# Main.net
KiCad netlist of a schematic drawn in Altium Designer
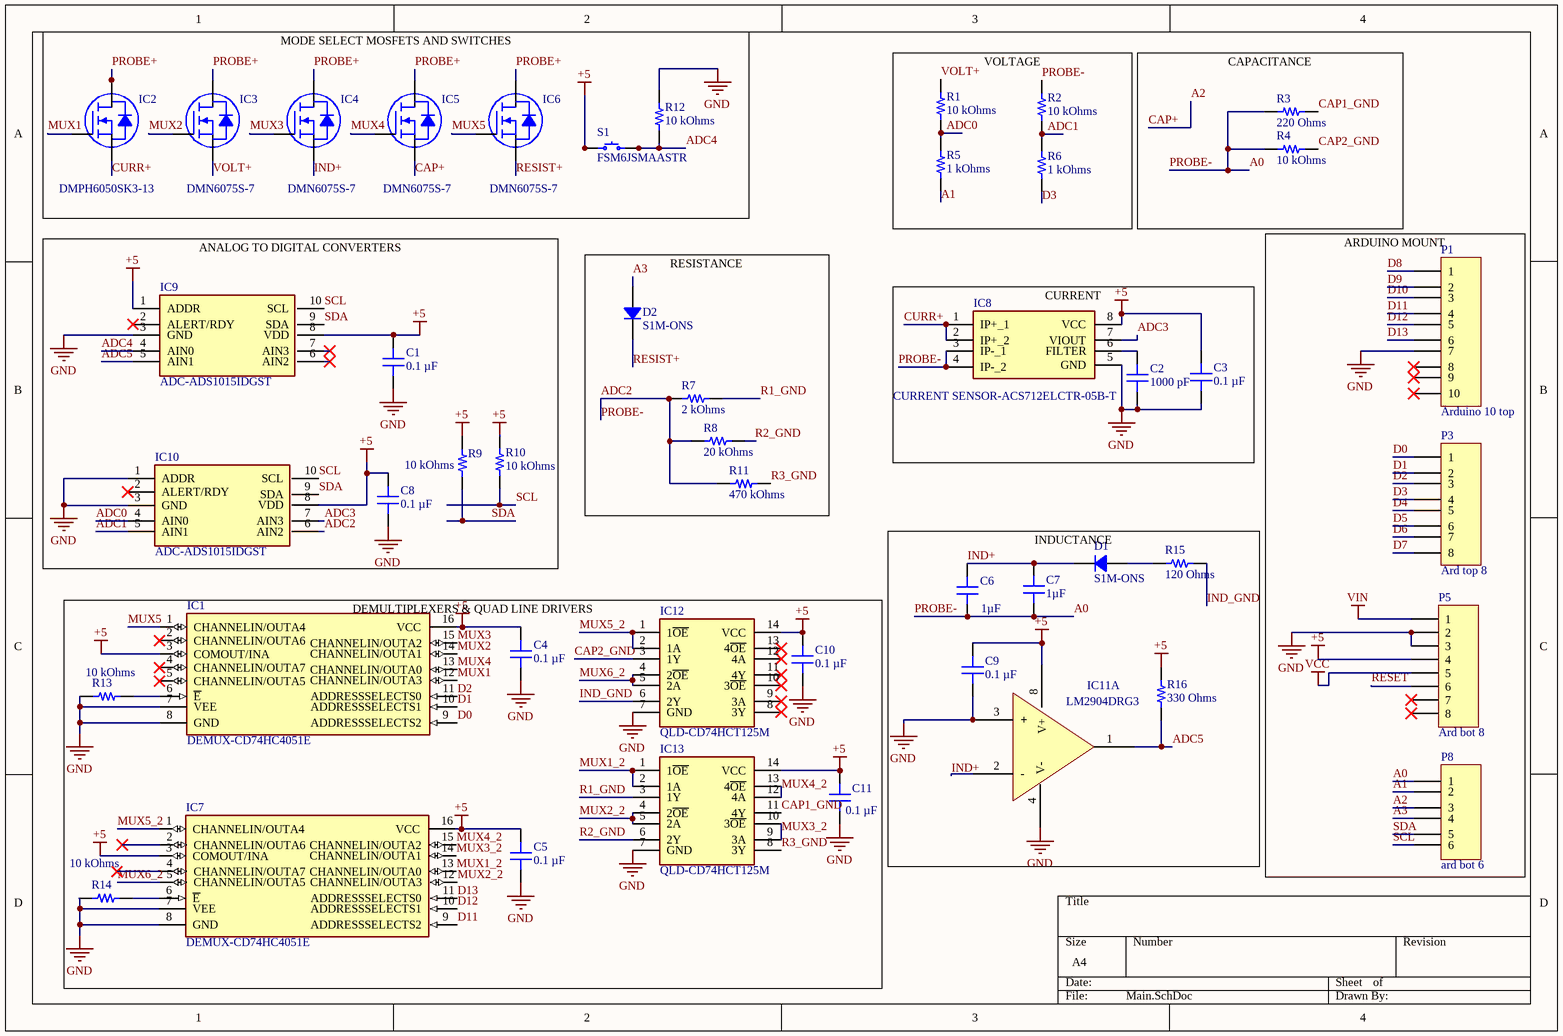
[diagram p0: Main.SchDoc]

(export (version "E")
  (design (tool "Eeschema 10.0.6"))
  (components
    (comp (ref "C1")
      (value "0.1 µF")
      (footprint "CAP 0805_2012")
      (description "CAP CER 0.1UF 50V X7R 0805")
      (fields
        (field (name "PART NUMBER") "CC0805MRX7R9BB104")
        (field (name "CAPACITANCE") "0.1 µF")
        (field (name "MANUFACTURER") "Yageo")
      )
      (libsource (lib "Celestial Altium Library - altium_library") (part "Capacitor"))
    )
    (comp (ref "C2")
      (value "1000 pF")
      (footprint "CAP 0805_2012")
      (description "CAP CER 1000PF 200V X7R 0805")
      (fields
        (field (name "PART NUMBER") "KGM21NR72D102KT")
        (field (name "CAPACITANCE") "1000 pF")
        (field (name "MANUFACTURER") "KYOCERA AVX")
      )
      (libsource (lib "Celestial Altium Library - altium_library") (part "Capacitor"))
    )
    (comp (ref "C3")
      (value "0.1 µF")
      (footprint "CAP 0805_2012")
      (description "CAP CER 0.1UF 50V X7R 0805")
      (fields
        (field (name "PART NUMBER") "CC0805MRX7R9BB104")
        (field (name "CAPACITANCE") "0.1 µF")
        (field (name "MANUFACTURER") "Yageo")
      )
      (libsource (lib "Celestial Altium Library - altium_library") (part "Capacitor"))
    )
    (comp (ref "C4")
      (value "0.1 µF")
      (footprint "CAP 0805_2012")
      (description "CAP CER 0.1UF 50V X7R 0805")
      (fields
        (field (name "PART NUMBER") "CC0805MRX7R9BB104")
        (field (name "CAPACITANCE") "0.1 µF")
        (field (name "MANUFACTURER") "Yageo")
      )
      (libsource (lib "Celestial Altium Library - altium_library") (part "Capacitor"))
    )
    (comp (ref "C5")
      (value "0.1 µF")
      (footprint "CAP 0805_2012")
      (description "CAP CER 0.1UF 50V X7R 0805")
      (fields
        (field (name "PART NUMBER") "CC0805MRX7R9BB104")
        (field (name "CAPACITANCE") "0.1 µF")
        (field (name "MANUFACTURER") "Yageo")
      )
      (libsource (lib "Celestial Altium Library - altium_library") (part "Capacitor"))
    )
    (comp (ref "C6")
      (value "1µF")
      (footprint "CAP 0805_2012")
      (description "CAP CER 1UF 10V X7R 0805")
      (fields
        (field (name "PART NUMBER") "MM05ZC105KCZ2A")
        (field (name "CAPACITANCE") "1µF")
        (field (name "MANUFACTURER") "AVX Corporation")
      )
      (libsource (lib "Celestial Altium Library - altium_library") (part "Capacitor"))
    )
    (comp (ref "C7")
      (value "1µF")
      (footprint "CAP 0805_2012")
      (description "CAP CER 1UF 10V X7R 0805")
      (fields
        (field (name "PART NUMBER") "MM05ZC105KCZ2A")
        (field (name "CAPACITANCE") "1µF")
        (field (name "MANUFACTURER") "AVX Corporation")
      )
      (libsource (lib "Celestial Altium Library - altium_library") (part "Capacitor"))
    )
    (comp (ref "C8")
      (value "0.1 µF")
      (footprint "CAP 0805_2012")
      (description "CAP CER 0.1UF 50V X7R 0805")
      (fields
        (field (name "PART NUMBER") "CC0805MRX7R9BB104")
        (field (name "CAPACITANCE") "0.1 µF")
        (field (name "MANUFACTURER") "Yageo")
      )
      (libsource (lib "Celestial Altium Library - altium_library") (part "Capacitor"))
    )
    (comp (ref "C9")
      (value "0.1 µF")
      (footprint "CAP 0805_2012")
      (description "CAP CER 0.1UF 50V X7R 0805")
      (fields
        (field (name "PART NUMBER") "CC0805MRX7R9BB104")
        (field (name "CAPACITANCE") "0.1 µF")
        (field (name "MANUFACTURER") "Yageo")
      )
      (libsource (lib "Celestial Altium Library - altium_library") (part "Capacitor"))
    )
    (comp (ref "C10")
      (value "0.1 µF")
      (footprint "CAP 0805_2012")
      (description "CAP CER 0.1UF 50V X7R 0805")
      (fields
        (field (name "PART NUMBER") "CC0805MRX7R9BB104")
        (field (name "CAPACITANCE") "0.1 µF")
        (field (name "MANUFACTURER") "Yageo")
      )
      (libsource (lib "Celestial Altium Library - altium_library") (part "Capacitor"))
    )
    (comp (ref "C11")
      (value "0.1 µF")
      (footprint "CAP 0805_2012")
      (description "CAP CER 0.1UF 50V X7R 0805")
      (fields
        (field (name "PART NUMBER") "CC0805MRX7R9BB104")
        (field (name "CAPACITANCE") "0.1 µF")
        (field (name "MANUFACTURER") "Yageo")
      )
      (libsource (lib "Celestial Altium Library - altium_library") (part "Capacitor"))
    )
    (comp (ref "D1")
      (value "S1M-ONS")
      (footprint "DO214AC SMA")
      (description "DIODE GEN PURP 50V 1A SMA")
      (fields (field (name "PART NUMBER") "RS1A") (field (name "MANUFACTURER") "ON Semiconductor"))
      (libsource (lib "Celestial Altium Library - altium_library") (part "Diode"))
    )
    (comp (ref "D2")
      (value "S1M-ONS")
      (footprint "DO214AC SMA")
      (description "DIODE GEN PURP 50V 1A SMA")
      (fields (field (name "PART NUMBER") "RS1A") (field (name "MANUFACTURER") "ON Semiconductor"))
      (libsource (lib "Celestial Altium Library - altium_library") (part "Diode"))
    )
    (comp (ref "IC1")
      (value "DEMUX-CD74HC4051E")
      (footprint "SamacSys:DIP794W53P254L1930H508Q16N")
      (description "Integrated Circuit")
      (fields
        (field (name "MANUFACTURER_PART_NUMBER") "CD74HC4051E")
        (field (name "MOUSER PART NUMBER") "595-CD74HC4051E")
      )
      (libsource (lib "*") (part "CD74HC4051E"))
    )
    (comp (ref "IC2")
      (value "DMPH6050SK3-13")
      (footprint "INFINEON PG-TO 252 GDS FET")
      (description "MOSFET N-CH 800V 1.9A TO252-3")
      (fields
        (field (name "PART NUMBER") "IPD80R2K8CEATMA1")
        (field (name "MANUFACTURER") "Infineon Technologies")
      )
      (libsource (lib "Celestial Altium Library - altium_library") (part "MOSFET SINGLE GDS"))
    )
    (comp (ref "IC3")
      (value "DMN6075S-7")
      (footprint "DIODES SOT-23-3")
      (description "MOSFET N-CH 60V 2A SOT23")
      (fields (field (name "MANUFACTURER") "Diodes Incorporated"))
      (libsource (lib "Celestial Altium Library - altium_library") (part "DIODES INC MOSFET N-CH SOT-23-3"))
    )
    (comp (ref "IC4")
      (value "DMN6075S-7")
      (footprint "DIODES SOT-23-3")
      (description "MOSFET N-CH 60V 2A SOT23")
      (fields (field (name "MANUFACTURER") "Diodes Incorporated"))
      (libsource (lib "Celestial Altium Library - altium_library") (part "DIODES INC MOSFET N-CH SOT-23-3"))
    )
    (comp (ref "IC5")
      (value "DMN6075S-7")
      (footprint "DIODES SOT-23-3")
      (description "MOSFET N-CH 60V 2A SOT23")
      (fields (field (name "MANUFACTURER") "Diodes Incorporated"))
      (libsource (lib "Celestial Altium Library - altium_library") (part "DIODES INC MOSFET N-CH SOT-23-3"))
    )
    (comp (ref "IC6")
      (value "DMN6075S-7")
      (footprint "DIODES SOT-23-3")
      (description "MOSFET N-CH 60V 2A SOT23")
      (fields (field (name "MANUFACTURER") "Diodes Incorporated"))
      (libsource (lib "Celestial Altium Library - altium_library") (part "DIODES INC MOSFET N-CH SOT-23-3"))
    )
    (comp (ref "IC7")
      (value "DEMUX-CD74HC4051E")
      (footprint "SamacSys:DIP794W53P254L1930H508Q16N")
      (description "Integrated Circuit")
      (fields
        (field (name "MANUFACTURER_PART_NUMBER") "CD74HC4051E")
        (field (name "MOUSER PART NUMBER") "595-CD74HC4051E")
      )
      (libsource (lib "") (part "CD74HC4051E_1"))
    )
    (comp (ref "IC8")
      (value "CURRENT SENSOR-ACS712ELCTR-05B-T")
      (footprint "SamacSys:SOIC127P600X175-8N")
      (description "Integrated Circuit")
      (fields
        (field (name "MANUFACTURER_PART_NUMBER") "ACS712ELCTR-05B-T")
        (field (name "MOUSER PART NUMBER") "250-712ELCTR05BT")
      )
      (libsource (lib "*") (part "ACS712ELCTR-05B-T"))
    )
    (comp (ref "IC9")
      (value "ADC-ADS1015IDGST")
      (footprint "SamacSys:SOP50P490X110-10N")
      (description "Integrated Circuit")
      (fields
        (field (name "MANUFACTURER_PART_NUMBER") "ADS1015IDGST")
        (field (name "MOUSER PART NUMBER") "595-ADS1015IDGST")
      )
      (libsource (lib "") (part "ADS1015IDGST_1"))
    )
    (comp (ref "IC10")
      (value "ADC-ADS1015IDGST")
      (footprint "SamacSys:SOP50P490X110-10N")
      (description "Integrated Circuit")
      (fields
        (field (name "MANUFACTURER_PART_NUMBER") "ADS1015IDGST")
        (field (name "MOUSER PART NUMBER") "595-ADS1015IDGST")
      )
      (libsource (lib "*") (part "ADS1015IDGST"))
    )
    (comp (ref "IC11")
      (value "LM2904DRG3")
      (footprint "TI SOIC-8 D")
      (description "IC OPAMP GP 2 CIRCUIT 8SOIC")
      (fields (field (name "MANUFACTURER") "Texas Instruments"))
      (libsource (lib "Celestial Altium Library - altium_library") (part "TI LM2904DR"))
    )
    (comp (ref "IC12")
      (value "QLD-CD74HCT125M")
      (footprint "SamacSys:SOIC127P600X175-14N")
      (description "Integrated Circuit")
      (fields
        (field (name "MANUFACTURER_PART_NUMBER") "CD74HCT125M")
        (field (name "MOUSER PART NUMBER") "595-CD74HCT125M")
      )
      (libsource (lib "*") (part "CD74HCT125M"))
    )
    (comp (ref "IC13")
      (value "QLD-CD74HCT125M")
      (footprint "SamacSys:SOIC127P600X175-14N")
      (description "Integrated Circuit")
      (fields
        (field (name "MANUFACTURER_PART_NUMBER") "CD74HCT125M")
        (field (name "MOUSER PART NUMBER") "595-CD74HCT125M")
      )
      (libsource (lib "") (part "CD74HCT125M_1"))
    )
    (comp (ref "P1")
      (value "Arduino 10 top")
      (footprint "HDR1X10")
      (description "Header, 10-Pin")
      (fields (field (name "PUBLISHER") "Altium Limited"))
      (libsource (lib "Miscellaneous Connectors") (part "Header 10"))
    )
    (comp (ref "P3")
      (value "Ard top 8")
      (footprint "HDR1X8")
      (description "Header, 8-Pin")
      (fields (field (name "PUBLISHER") "Altium Limited"))
      (libsource (lib "") (part "Header 8_1"))
    )
    (comp (ref "P5")
      (value "Ard bot 8")
      (footprint "HDR1X8")
      (description "Header, 8-Pin")
      (fields (field (name "PUBLISHER") "Altium Limited"))
      (libsource (lib "Miscellaneous Connectors") (part "Header 8"))
    )
    (comp (ref "P8")
      (value "ard bot 6")
      (footprint "HDR1X6")
      (description "Header, 6-Pin")
      (fields (field (name "PUBLISHER") "Altium Limited"))
      (libsource (lib "Miscellaneous Connectors") (part "Header 6"))
    )
    (comp (ref "R1")
      (value "10 kOhms")
      (footprint "RES 0805_2012")
      (description "RES 10K OHM 0.1% 1/10W 0805")
      (fields
        (field (name "PART NUMBER") "RNCS0805BKE10K0")
        (field (name "MANUFACTURER") "Stackpole Electronics Inc")
      )
      (libsource (lib "Celestial Altium Library - altium_library") (part "Resistor"))
    )
    (comp (ref "R2")
      (value "10 kOhms")
      (footprint "RES 0805_2012")
      (description "RES 10K OHM 0.1% 1/10W 0805")
      (fields
        (field (name "PART NUMBER") "RNCS0805BKE10K0")
        (field (name "MANUFACTURER") "Stackpole Electronics Inc")
      )
      (libsource (lib "Celestial Altium Library - altium_library") (part "Resistor"))
    )
    (comp (ref "R3")
      (value "220 Ohms")
      (footprint "RES 0805_2012")
      (description "RES SMD 220 OHM 1% 0.4W 0805")
      (fields (field (name "PART NUMBER") "ESR10EZPF2200") (field (name "MANUFACTURER") "Rohm Semiconductor"))
      (libsource (lib "Celestial Altium Library - altium_library") (part "Resistor"))
    )
    (comp (ref "R4")
      (value "10 kOhms")
      (footprint "RES 0805_2012")
      (description "RES 10K OHM 0.1% 1/10W 0805")
      (fields
        (field (name "PART NUMBER") "RNCS0805BKE10K0")
        (field (name "MANUFACTURER") "Stackpole Electronics Inc")
      )
      (libsource (lib "Celestial Altium Library - altium_library") (part "Resistor"))
    )
    (comp (ref "R5")
      (value "1 kOhms")
      (footprint "RES 0805_2012")
      (description "RES 10K OHM 0.1% 1/10W 0805")
      (fields
        (field (name "PART NUMBER") "RNCS0805BKE10K0")
        (field (name "MANUFACTURER") "Stackpole Electronics Inc")
      )
      (libsource (lib "Celestial Altium Library - altium_library") (part "Resistor"))
    )
    (comp (ref "R6")
      (value "1 kOhms")
      (footprint "RES 0805_2012")
      (description "RES 10K OHM 0.1% 1/10W 0805")
      (fields
        (field (name "PART NUMBER") "RNCS0805BKE10K0")
        (field (name "MANUFACTURER") "Stackpole Electronics Inc")
      )
      (libsource (lib "Celestial Altium Library - altium_library") (part "Resistor"))
    )
    (comp (ref "R7")
      (value "2 kOhms")
      (footprint "RES 0805_2012")
      (description "RES 10K OHM 0.1% 1/10W 0805")
      (fields
        (field (name "PART NUMBER") "RNCS0805BKE10K0")
        (field (name "MANUFACTURER") "Stackpole Electronics Inc")
      )
      (libsource (lib "Celestial Altium Library - altium_library") (part "Resistor"))
    )
    (comp (ref "R8")
      (value "20 kOhms")
      (footprint "RES 0805_2012")
      (description "RES 10K OHM 0.1% 1/10W 0805")
      (fields
        (field (name "PART NUMBER") "RNCS0805BKE10K0")
        (field (name "MANUFACTURER") "Stackpole Electronics Inc")
      )
      (libsource (lib "Celestial Altium Library - altium_library") (part "Resistor"))
    )
    (comp (ref "R9")
      (value "10 kOhms")
      (footprint "RES 0805_2012")
      (description "RES 10K OHM 0.1% 1/10W 0805")
      (fields
        (field (name "PART NUMBER") "RNCS0805BKE10K0")
        (field (name "MANUFACTURER") "Stackpole Electronics Inc")
      )
      (libsource (lib "Celestial Altium Library - altium_library") (part "Resistor"))
    )
    (comp (ref "R10")
      (value "10 kOhms")
      (footprint "RES 0805_2012")
      (description "RES 10K OHM 0.1% 1/10W 0805")
      (fields
        (field (name "PART NUMBER") "RNCS0805BKE10K0")
        (field (name "MANUFACTURER") "Stackpole Electronics Inc")
      )
      (libsource (lib "Celestial Altium Library - altium_library") (part "Resistor"))
    )
    (comp (ref "R11")
      (value "470 kOhms")
      (footprint "RES 0805_2012")
      (description "RES 10K OHM 0.1% 1/10W 0805")
      (fields
        (field (name "PART NUMBER") "RNCS0805BKE10K0")
        (field (name "MANUFACTURER") "Stackpole Electronics Inc")
      )
      (libsource (lib "Celestial Altium Library - altium_library") (part "Resistor"))
    )
    (comp (ref "R12")
      (value "10 kOhms")
      (footprint "RES 0805_2012")
      (description "RES 10K OHM 0.1% 1/10W 0805")
      (fields
        (field (name "PART NUMBER") "RNCS0805BKE10K0")
        (field (name "MANUFACTURER") "Stackpole Electronics Inc")
      )
      (libsource (lib "Celestial Altium Library - altium_library") (part "Resistor"))
    )
    (comp (ref "R13")
      (value "10 kOhms")
      (footprint "RES 0805_2012")
      (description "RES 10K OHM 0.1% 1/10W 0805")
      (fields
        (field (name "PART NUMBER") "RNCS0805BKE10K0")
        (field (name "MANUFACTURER") "Stackpole Electronics Inc")
      )
      (libsource (lib "Celestial Altium Library - altium_library") (part "Resistor"))
    )
    (comp (ref "R14")
      (value "10 kOhms")
      (footprint "RES 0805_2012")
      (description "RES 10K OHM 0.1% 1/10W 0805")
      (fields
        (field (name "PART NUMBER") "RNCS0805BKE10K0")
        (field (name "MANUFACTURER") "Stackpole Electronics Inc")
      )
      (libsource (lib "Celestial Altium Library - altium_library") (part "Resistor"))
    )
    (comp (ref "R15")
      (value "120 Ohms")
      (footprint "RES 0805_2012")
      (description "RES SMD 120 OHM 1% 1/8W 0805")
      (fields
        (field (name "PART NUMBER") "ERJ-6ENF1200V")
        (field (name "MANUFACTURER") "Panasonic Electronic Components")
      )
      (libsource (lib "Celestial Altium Library - altium_library") (part "Resistor"))
    )
    (comp (ref "R16")
      (value "330 Ohms")
      (footprint "RES 0805_2012")
      (description "RES SMD 330 OHM 1% 1/2W 0805")
      (fields (field (name "PART NUMBER") "CRCW0805330RFKEAHP") (field (name "MANUFACTURER") "Vishay Dale"))
      (libsource (lib "Celestial Altium Library - altium_library") (part "Resistor"))
    )
    (comp (ref "S1")
      (value "FSM6JSMAASTR")
      (footprint "TE FSM6JSMA")
      (description "SWITCH TACTILE SPST-NO 0.05A 24V")
      (fields (field (name "MANUFACTURER") "TE Connectivity ALCOSWITCH Switches"))
      (libsource (lib "Celestial Altium Library - altium_library") (part "SPST-NO 4 PIN"))
    )
  )
  (nets
    (net (code "1") (name "+5") (class "Default")
      (node (ref "C1") (pin "2") (pinfunction "2_2") (pintype "passive"))
      (node (ref "C10") (pin "2") (pinfunction "2_2") (pintype "passive"))
      (node (ref "C11") (pin "2") (pinfunction "2_2") (pintype "passive"))
      (node (ref "C3") (pin "2") (pinfunction "2_2") (pintype "passive"))
      (node (ref "C4") (pin "2") (pinfunction "2_2") (pintype "passive"))
      (node (ref "C5") (pin "2") (pinfunction "2_2") (pintype "passive"))
      (node (ref "C8") (pin "2") (pinfunction "2_2") (pintype "passive"))
      (node (ref "C9") (pin "2") (pinfunction "2_2") (pintype "passive"))
      (node (ref "IC1") (pin "16") (pinfunction "VCC_16") (pintype "power_in"))
      (node (ref "IC1") (pin "3") (pinfunction "COMOUT/INA_3") (pintype "bidirectional"))
      (node (ref "IC10") (pin "8") (pinfunction "VDD_8") (pintype "passive"))
      (node (ref "IC11") (pin "8") (pinfunction "V+_8") (pintype "passive"))
      (node (ref "IC12") (pin "14") (pinfunction "VCC_14") (pintype "passive"))
      (node (ref "IC13") (pin "14") (pinfunction "VCC_14") (pintype "passive"))
      (node (ref "IC7") (pin "16") (pinfunction "VCC_16") (pintype "power_in"))
      (node (ref "IC7") (pin "3") (pinfunction "COMOUT/INA_3") (pintype "bidirectional"))
      (node (ref "IC8") (pin "8") (pinfunction "VCC_8") (pintype "passive"))
      (node (ref "IC9") (pin "1") (pinfunction "ADDR_1") (pintype "passive"))
      (node (ref "IC9") (pin "8") (pinfunction "VDD_8") (pintype "passive"))
      (node (ref "P5") (pin "4") (pinfunction "4_4") (pintype "passive"))
      (node (ref "R10") (pin "2") (pinfunction "2_2") (pintype "passive"))
      (node (ref "R16") (pin "2") (pinfunction "2_2") (pintype "passive"))
      (node (ref "R9") (pin "2") (pinfunction "2_2") (pintype "passive"))
      (node (ref "S1") (pin "1") (pinfunction "1_1") (pintype "passive"))
      (node (ref "S1") (pin "2") (pinfunction "2_2") (pintype "passive"))
    )
    (net (code "2") (name "/A0") (class "Default")
      (node (ref "C6") (pin "1") (pinfunction "1_1") (pintype "passive"))
      (node (ref "C7") (pin "1") (pinfunction "1_1") (pintype "passive"))
      (node (ref "IC10") (pin "6") (pinfunction "AIN2_6") (pintype "passive"))
      (node (ref "IC8") (pin "3") (pinfunction "IP-_1_3") (pintype "passive"))
      (node (ref "IC8") (pin "4") (pinfunction "IP-_2_4") (pintype "passive"))
      (node (ref "P8") (pin "1") (pinfunction "1_1") (pintype "passive"))
      (node (ref "R11") (pin "2") (pinfunction "2_2") (pintype "passive"))
      (node (ref "R2") (pin "2") (pinfunction "2_2") (pintype "passive"))
      (node (ref "R3") (pin "1") (pinfunction "1_1") (pintype "passive"))
      (node (ref "R4") (pin "2") (pinfunction "2_2") (pintype "passive"))
      (node (ref "R7") (pin "2") (pinfunction "2_2") (pintype "passive"))
      (node (ref "R8") (pin "2") (pinfunction "2_2") (pintype "passive"))
    )
    (net (code "3") (name "/A1") (class "Default")
      (node (ref "P8") (pin "2") (pinfunction "2_2") (pintype "passive"))
      (node (ref "R5") (pin "1") (pinfunction "1_1") (pintype "passive"))
    )
    (net (code "4") (name "/A2") (class "Default")
      (node (ref "IC5") (pin "2") (pinfunction "S_2") (pintype "passive"))
      (node (ref "P8") (pin "3") (pinfunction "3_3") (pintype "passive"))
    )
    (net (code "5") (name "/A3") (class "Default")
      (node (ref "D2") (pin "1") (pinfunction "1_1") (pintype "passive"))
      (node (ref "P8") (pin "4") (pinfunction "4_4") (pintype "passive"))
    )
    (net (code "6") (name "/ADC0") (class "Default")
      (node (ref "IC10") (pin "4") (pinfunction "AIN0_4") (pintype "passive"))
      (node (ref "R1") (pin "1") (pinfunction "1_1") (pintype "passive"))
      (node (ref "R5") (pin "2") (pinfunction "2_2") (pintype "passive"))
    )
    (net (code "7") (name "/ADC1") (class "Default")
      (node (ref "IC10") (pin "5") (pinfunction "AIN1_5") (pintype "passive"))
      (node (ref "R2") (pin "1") (pinfunction "1_1") (pintype "passive"))
      (node (ref "R6") (pin "2") (pinfunction "2_2") (pintype "passive"))
    )
    (net (code "8") (name "/ADC3") (class "Default")
      (node (ref "IC10") (pin "7") (pinfunction "AIN3_7") (pintype "passive"))
      (node (ref "IC8") (pin "7") (pinfunction "VIOUT_7") (pintype "passive"))
    )
    (net (code "9") (name "/ADC4") (class "Default")
      (node (ref "IC9") (pin "4") (pinfunction "AIN0_4") (pintype "passive"))
      (node (ref "R12") (pin "1") (pinfunction "1_1") (pintype "passive"))
      (node (ref "S1") (pin "3") (pinfunction "3_3") (pintype "passive"))
      (node (ref "S1") (pin "4") (pinfunction "4_4") (pintype "passive"))
    )
    (net (code "10") (name "/ADC5") (class "Default")
      (node (ref "IC11") (pin "1") (pinfunction "OUTA_1") (pintype "passive"))
      (node (ref "IC9") (pin "5") (pinfunction "AIN1_5") (pintype "passive"))
      (node (ref "R16") (pin "1") (pinfunction "1_1") (pintype "passive"))
    )
    (net (code "11") (name "/CAP1_GND") (class "Default")
      (node (ref "IC13") (pin "11") (pinfunction "4Y_11") (pintype "passive"))
      (node (ref "R3") (pin "2") (pinfunction "2_2") (pintype "passive"))
    )
    (net (code "12") (name "/CAP2_GND") (class "Default")
      (node (ref "IC12") (pin "3") (pinfunction "1Y_3") (pintype "passive"))
      (node (ref "R4") (pin "1") (pinfunction "1_1") (pintype "passive"))
    )
    (net (code "13") (name "/CURR+") (class "Default")
      (node (ref "IC2") (pin "S") (pinfunction "S_S") (pintype "passive"))
      (node (ref "IC8") (pin "1") (pinfunction "IP+_1_1") (pintype "passive"))
      (node (ref "IC8") (pin "2") (pinfunction "IP+_2_2") (pintype "passive"))
    )
    (net (code "14") (name "/D0") (class "Default")
      (node (ref "IC1") (pin "9") (pinfunction "ADDRESSSELECTS2_9") (pintype "input"))
      (node (ref "P3") (pin "1") (pinfunction "1_1") (pintype "passive"))
    )
    (net (code "15") (name "/D1") (class "Default")
      (node (ref "IC1") (pin "10") (pinfunction "ADDRESSSELECTS1_10") (pintype "input"))
      (node (ref "P3") (pin "2") (pinfunction "2_2") (pintype "passive"))
    )
    (net (code "16") (name "/D2") (class "Default")
      (node (ref "IC1") (pin "11") (pinfunction "ADDRESSSELECTS0_11") (pintype "input"))
      (node (ref "P3") (pin "3") (pinfunction "3_3") (pintype "passive"))
    )
    (net (code "17") (name "/D3") (class "Default")
      (node (ref "P3") (pin "4") (pinfunction "4_4") (pintype "passive"))
      (node (ref "R6") (pin "1") (pinfunction "1_1") (pintype "passive"))
    )
    (net (code "18") (name "/D4") (class "Default")
      (node (ref "P3") (pin "5") (pinfunction "5_5") (pintype "passive"))
    )
    (net (code "19") (name "/D5") (class "Default")
      (node (ref "P3") (pin "6") (pinfunction "6_6") (pintype "passive"))
    )
    (net (code "20") (name "/D6") (class "Default")
      (node (ref "P3") (pin "7") (pinfunction "7_7") (pintype "passive"))
    )
    (net (code "21") (name "/D7") (class "Default")
      (node (ref "P3") (pin "8") (pinfunction "8_8") (pintype "passive"))
    )
    (net (code "22") (name "/D8") (class "Default")
      (node (ref "P1") (pin "1") (pinfunction "1_1") (pintype "passive"))
    )
    (net (code "23") (name "/D9") (class "Default")
      (node (ref "P1") (pin "2") (pinfunction "2_2") (pintype "passive"))
    )
    (net (code "24") (name "/D10") (class "Default")
      (node (ref "P1") (pin "3") (pinfunction "3_3") (pintype "passive"))
    )
    (net (code "25") (name "/D11") (class "Default")
      (node (ref "IC7") (pin "9") (pinfunction "ADDRESSSELECTS2_9") (pintype "input"))
      (node (ref "P1") (pin "4") (pinfunction "4_4") (pintype "passive"))
    )
    (net (code "26") (name "/D12") (class "Default")
      (node (ref "IC7") (pin "10") (pinfunction "ADDRESSSELECTS1_10") (pintype "input"))
      (node (ref "P1") (pin "5") (pinfunction "5_5") (pintype "passive"))
    )
    (net (code "27") (name "/D13") (class "Default")
      (node (ref "IC7") (pin "11") (pinfunction "ADDRESSSELECTS0_11") (pintype "input"))
      (node (ref "P1") (pin "6") (pinfunction "6_6") (pintype "passive"))
    )
    (net (code "28") (name "/IND+") (class "Default")
      (node (ref "C6") (pin "2") (pinfunction "2_2") (pintype "passive"))
      (node (ref "C7") (pin "2") (pinfunction "2_2") (pintype "passive"))
      (node (ref "D1") (pin "2") (pinfunction "2_2") (pintype "passive"))
      (node (ref "IC11") (pin "2") (pinfunction "-_2") (pintype "passive"))
      (node (ref "IC4") (pin "2") (pinfunction "S_2") (pintype "passive"))
    )
    (net (code "29") (name "/IND_GND") (class "Default")
      (node (ref "IC12") (pin "6") (pinfunction "2Y_6") (pintype "passive"))
      (node (ref "R15") (pin "2") (pinfunction "2_2") (pintype "passive"))
    )
    (net (code "30") (name "/MUX1") (class "Default")
      (node (ref "IC1") (pin "12") (pinfunction "CHANNELIN/OUTA3_12") (pintype "bidirectional"))
      (node (ref "IC2") (pin "G") (pinfunction "G_G") (pintype "passive"))
    )
    (net (code "31") (name "/MUX1_2") (class "Default")
      (node (ref "IC13") (pin "1") (pinfunction "1~{OE}_1") (pintype "passive"))
      (node (ref "IC13") (pin "2") (pinfunction "1A_2") (pintype "passive"))
      (node (ref "IC7") (pin "13") (pinfunction "CHANNELIN/OUTA0_13") (pintype "bidirectional"))
    )
    (net (code "32") (name "/MUX2") (class "Default")
      (node (ref "IC1") (pin "14") (pinfunction "CHANNELIN/OUTA1_14") (pintype "bidirectional"))
      (node (ref "IC3") (pin "1") (pinfunction "G_1") (pintype "passive"))
    )
    (net (code "33") (name "/MUX2_2") (class "Default")
      (node (ref "IC13") (pin "4") (pinfunction "2~{OE}_4") (pintype "passive"))
      (node (ref "IC13") (pin "5") (pinfunction "2A_5") (pintype "passive"))
      (node (ref "IC7") (pin "12") (pinfunction "CHANNELIN/OUTA3_12") (pintype "bidirectional"))
    )
    (net (code "34") (name "/MUX3") (class "Default")
      (node (ref "IC1") (pin "15") (pinfunction "CHANNELIN/OUTA2_15") (pintype "bidirectional"))
      (node (ref "IC4") (pin "1") (pinfunction "G_1") (pintype "passive"))
    )
    (net (code "35") (name "/MUX3_2") (class "Default")
      (node (ref "IC13") (pin "10") (pinfunction "3~{OE}_10") (pintype "passive"))
      (node (ref "IC13") (pin "9") (pinfunction "3A_9") (pintype "passive"))
      (node (ref "IC7") (pin "14") (pinfunction "CHANNELIN/OUTA1_14") (pintype "bidirectional"))
    )
    (net (code "36") (name "/MUX4") (class "Default")
      (node (ref "IC1") (pin "13") (pinfunction "CHANNELIN/OUTA0_13") (pintype "bidirectional"))
      (node (ref "IC5") (pin "1") (pinfunction "G_1") (pintype "passive"))
    )
    (net (code "37") (name "/MUX4_2") (class "Default")
      (node (ref "IC13") (pin "12") (pinfunction "4A_12") (pintype "passive"))
      (node (ref "IC13") (pin "13") (pinfunction "4~{OE}_13") (pintype "passive"))
      (node (ref "IC7") (pin "15") (pinfunction "CHANNELIN/OUTA2_15") (pintype "bidirectional"))
    )
    (net (code "38") (name "/MUX5") (class "Default")
      (node (ref "IC1") (pin "1") (pinfunction "CHANNELIN/OUTA4_1") (pintype "bidirectional"))
      (node (ref "IC6") (pin "1") (pinfunction "G_1") (pintype "passive"))
    )
    (net (code "39") (name "/MUX5_2") (class "Default")
      (node (ref "IC12") (pin "1") (pinfunction "1~{OE}_1") (pintype "passive"))
      (node (ref "IC12") (pin "2") (pinfunction "1A_2") (pintype "passive"))
      (node (ref "IC7") (pin "1") (pinfunction "CHANNELIN/OUTA4_1") (pintype "bidirectional"))
    )
    (net (code "40") (name "/MUX6_2") (class "Default")
      (node (ref "IC12") (pin "4") (pinfunction "2~{OE}_4") (pintype "passive"))
      (node (ref "IC12") (pin "5") (pinfunction "2A_5") (pintype "passive"))
      (node (ref "IC7") (pin "5") (pinfunction "CHANNELIN/OUTA5_5") (pintype "bidirectional"))
    )
    (net (code "41") (name "/PROBE+") (class "Default")
      (node (ref "IC2") (pin "D") (pinfunction "D_D") (pintype "passive"))
      (node (ref "IC3") (pin "3") (pinfunction "D_3") (pintype "passive"))
      (node (ref "IC4") (pin "3") (pinfunction "D_3") (pintype "passive"))
      (node (ref "IC5") (pin "3") (pinfunction "D_3") (pintype "passive"))
      (node (ref "IC6") (pin "3") (pinfunction "D_3") (pintype "passive"))
    )
    (net (code "42") (name "/R1_GND") (class "Default")
      (node (ref "IC13") (pin "3") (pinfunction "1Y_3") (pintype "passive"))
      (node (ref "R7") (pin "1") (pinfunction "1_1") (pintype "passive"))
    )
    (net (code "43") (name "/R2_GND") (class "Default")
      (node (ref "IC13") (pin "6") (pinfunction "2Y_6") (pintype "passive"))
      (node (ref "R8") (pin "1") (pinfunction "1_1") (pintype "passive"))
    )
    (net (code "44") (name "/R3_GND") (class "Default")
      (node (ref "IC13") (pin "8") (pinfunction "3Y_8") (pintype "passive"))
      (node (ref "R11") (pin "1") (pinfunction "1_1") (pintype "passive"))
    )
    (net (code "45") (name "/RESET") (class "Default")
      (node (ref "P5") (pin "6") (pinfunction "6_6") (pintype "passive"))
    )
    (net (code "46") (name "/RESIST+") (class "Default")
      (node (ref "D2") (pin "2") (pinfunction "2_2") (pintype "passive"))
      (node (ref "IC6") (pin "2") (pinfunction "S_2") (pintype "passive"))
    )
    (net (code "47") (name "/SCL") (class "Default")
      (node (ref "IC10") (pin "10") (pinfunction "SCL_10") (pintype "passive"))
      (node (ref "IC9") (pin "10") (pinfunction "SCL_10") (pintype "passive"))
      (node (ref "P8") (pin "6") (pinfunction "6_6") (pintype "passive"))
      (node (ref "R10") (pin "1") (pinfunction "1_1") (pintype "passive"))
    )
    (net (code "48") (name "/SDA") (class "Default")
      (node (ref "IC10") (pin "9") (pinfunction "SDA_9") (pintype "passive"))
      (node (ref "IC9") (pin "9") (pinfunction "SDA_9") (pintype "passive"))
      (node (ref "P8") (pin "5") (pinfunction "5_5") (pintype "passive"))
      (node (ref "R9") (pin "1") (pinfunction "1_1") (pintype "passive"))
    )
    (net (code "49") (name "/VOLT+") (class "Default")
      (node (ref "IC3") (pin "2") (pinfunction "S_2") (pintype "passive"))
      (node (ref "R1") (pin "2") (pinfunction "2_2") (pintype "passive"))
    )
    (net (code "50") (name "GND") (class "Default")
      (node (ref "C1") (pin "1") (pinfunction "1_1") (pintype "passive"))
      (node (ref "C10") (pin "1") (pinfunction "1_1") (pintype "passive"))
      (node (ref "C11") (pin "1") (pinfunction "1_1") (pintype "passive"))
      (node (ref "C2") (pin "1") (pinfunction "1_1") (pintype "passive"))
      (node (ref "C3") (pin "1") (pinfunction "1_1") (pintype "passive"))
      (node (ref "C4") (pin "1") (pinfunction "1_1") (pintype "passive"))
      (node (ref "C5") (pin "1") (pinfunction "1_1") (pintype "passive"))
      (node (ref "C8") (pin "1") (pinfunction "1_1") (pintype "passive"))
      (node (ref "C9") (pin "1") (pinfunction "1_1") (pintype "passive"))
      (node (ref "IC1") (pin "7") (pinfunction "VEE_7") (pintype "power_in"))
      (node (ref "IC1") (pin "8") (pinfunction "GND_8") (pintype "power_in"))
      (node (ref "IC10") (pin "1") (pinfunction "ADDR_1") (pintype "passive"))
      (node (ref "IC10") (pin "3") (pinfunction "GND_3") (pintype "passive"))
      (node (ref "IC11") (pin "3") (pinfunction "+_3") (pintype "passive"))
      (node (ref "IC11") (pin "4") (pinfunction "V-_4") (pintype "passive"))
      (node (ref "IC12") (pin "7") (pinfunction "GND_7") (pintype "passive"))
      (node (ref "IC13") (pin "7") (pinfunction "GND_7") (pintype "passive"))
      (node (ref "IC7") (pin "7") (pinfunction "VEE_7") (pintype "power_in"))
      (node (ref "IC7") (pin "8") (pinfunction "GND_8") (pintype "power_in"))
      (node (ref "IC8") (pin "5") (pinfunction "GND_5") (pintype "passive"))
      (node (ref "IC9") (pin "3") (pinfunction "GND_3") (pintype "passive"))
      (node (ref "P1") (pin "7") (pinfunction "7_7") (pintype "passive"))
      (node (ref "P5") (pin "2") (pinfunction "2_2") (pintype "passive"))
      (node (ref "P5") (pin "3") (pinfunction "3_3") (pintype "passive"))
      (node (ref "R12") (pin "2") (pinfunction "2_2") (pintype "passive"))
      (node (ref "R13") (pin "2") (pinfunction "2_2") (pintype "passive"))
      (node (ref "R14") (pin "2") (pinfunction "2_2") (pintype "passive"))
    )
    (net (code "51") (name "Net-(D1-Pad1)") (class "Default")
      (node (ref "D1") (pin "1") (pinfunction "1_1") (pintype "passive"))
      (node (ref "R15") (pin "1") (pinfunction "1_1") (pintype "passive"))
    )
    (net (code "52") (name "Net-(IC1-~{E})") (class "Default")
      (node (ref "IC1") (pin "6") (pinfunction "~{E}_6") (pintype "input"))
      (node (ref "R13") (pin "1") (pinfunction "1_1") (pintype "passive"))
    )
    (net (code "53") (name "Net-(IC7-~{E})") (class "Default")
      (node (ref "IC7") (pin "6") (pinfunction "~{E}_6") (pintype "input"))
      (node (ref "R14") (pin "1") (pinfunction "1_1") (pintype "passive"))
    )
    (net (code "54") (name "Net-(IC8-FILTER)") (class "Default")
      (node (ref "C2") (pin "2") (pinfunction "2_2") (pintype "passive"))
      (node (ref "IC8") (pin "6") (pinfunction "FILTER_6") (pintype "passive"))
    )
    (net (code "55") (name "VCC") (class "Default")
      (node (ref "P5") (pin "5") (pinfunction "5_5") (pintype "passive"))
    )
    (net (code "56") (name "VIN") (class "Default")
      (node (ref "P5") (pin "1") (pinfunction "1_1") (pintype "passive"))
    )
    (net (code "57") (name "unconnected-(IC1-CHANNELIN{slash}OUTA5-Pad5)") (class "Default")
      (node (ref "IC1") (pin "5") (pinfunction "CHANNELIN/OUTA5_5") (pintype "bidirectional+no_connect"))
    )
    (net (code "58") (name "unconnected-(IC1-CHANNELIN{slash}OUTA6-Pad2)") (class "Default")
      (node (ref "IC1") (pin "2") (pinfunction "CHANNELIN/OUTA6_2") (pintype "bidirectional+no_connect"))
    )
    (net (code "59") (name "unconnected-(IC1-CHANNELIN{slash}OUTA7-Pad4)") (class "Default")
      (node (ref "IC1") (pin "4") (pinfunction "CHANNELIN/OUTA7_4") (pintype "bidirectional+no_connect"))
    )
    (net (code "60") (name "unconnected-(IC7-CHANNELIN{slash}OUTA6-Pad2)") (class "Default")
      (node (ref "IC7") (pin "2") (pinfunction "CHANNELIN/OUTA6_2") (pintype "bidirectional+no_connect"))
    )
    (net (code "61") (name "unconnected-(IC7-CHANNELIN{slash}OUTA7-Pad4)") (class "Default")
      (node (ref "IC7") (pin "4") (pinfunction "CHANNELIN/OUTA7_4") (pintype "bidirectional+no_connect"))
    )
    (net (code "62") (name "unconnected-(IC9-AIN2-Pad6)") (class "Default")
      (node (ref "IC9") (pin "6") (pinfunction "AIN2_6") (pintype "passive+no_connect"))
    )
    (net (code "63") (name "unconnected-(IC9-AIN3-Pad7)") (class "Default")
      (node (ref "IC9") (pin "7") (pinfunction "AIN3_7") (pintype "passive+no_connect"))
    )
    (net (code "64") (name "unconnected-(IC9-ALERT{slash}RDY-Pad2)") (class "Default")
      (node (ref "IC9") (pin "2") (pinfunction "ALERT/RDY_2") (pintype "passive+no_connect"))
    )
    (net (code "65") (name "unconnected-(IC10-ALERT{slash}RDY-Pad2)") (class "Default")
      (node (ref "IC10") (pin "2") (pinfunction "ALERT/RDY_2") (pintype "passive+no_connect"))
    )
    (net (code "66") (name "unconnected-(IC12-3A-Pad9)") (class "Default")
      (node (ref "IC12") (pin "9") (pinfunction "3A_9") (pintype "passive+no_connect"))
    )
    (net (code "67") (name "unconnected-(IC12-3Y-Pad8)") (class "Default")
      (node (ref "IC12") (pin "8") (pinfunction "3Y_8") (pintype "passive+no_connect"))
    )
    (net (code "68") (name "unconnected-(IC12-3~{OE}-Pad10)") (class "Default")
      (node (ref "IC12") (pin "10") (pinfunction "3~{OE}_10") (pintype "passive+no_connect"))
    )
    (net (code "69") (name "unconnected-(IC12-4A-Pad12)") (class "Default")
      (node (ref "IC12") (pin "12") (pinfunction "4A_12") (pintype "passive+no_connect"))
    )
    (net (code "70") (name "unconnected-(IC12-4Y-Pad11)") (class "Default")
      (node (ref "IC12") (pin "11") (pinfunction "4Y_11") (pintype "passive+no_connect"))
    )
    (net (code "71") (name "unconnected-(IC12-4~{OE}-Pad13)") (class "Default")
      (node (ref "IC12") (pin "13") (pinfunction "4~{OE}_13") (pintype "passive+no_connect"))
    )
    (net (code "72") (name "unconnected-(P1-Pad8)") (class "Default")
      (node (ref "P1") (pin "8") (pinfunction "8_8") (pintype "passive+no_connect"))
    )
    (net (code "73") (name "unconnected-(P1-Pad9)") (class "Default")
      (node (ref "P1") (pin "9") (pinfunction "9_9") (pintype "passive+no_connect"))
    )
    (net (code "74") (name "unconnected-(P1-Pad10)") (class "Default")
      (node (ref "P1") (pin "10") (pinfunction "10_10") (pintype "passive+no_connect"))
    )
    (net (code "75") (name "unconnected-(P5-Pad7)") (class "Default")
      (node (ref "P5") (pin "7") (pinfunction "7_7") (pintype "passive+no_connect"))
    )
    (net (code "76") (name "unconnected-(P5-Pad8)") (class "Default")
      (node (ref "P5") (pin "8") (pinfunction "8_8") (pintype "passive+no_connect"))
    )
  )
)
